# LEDs_Switches.net
KiCad netlist of a schematic drawn in Altium Designer
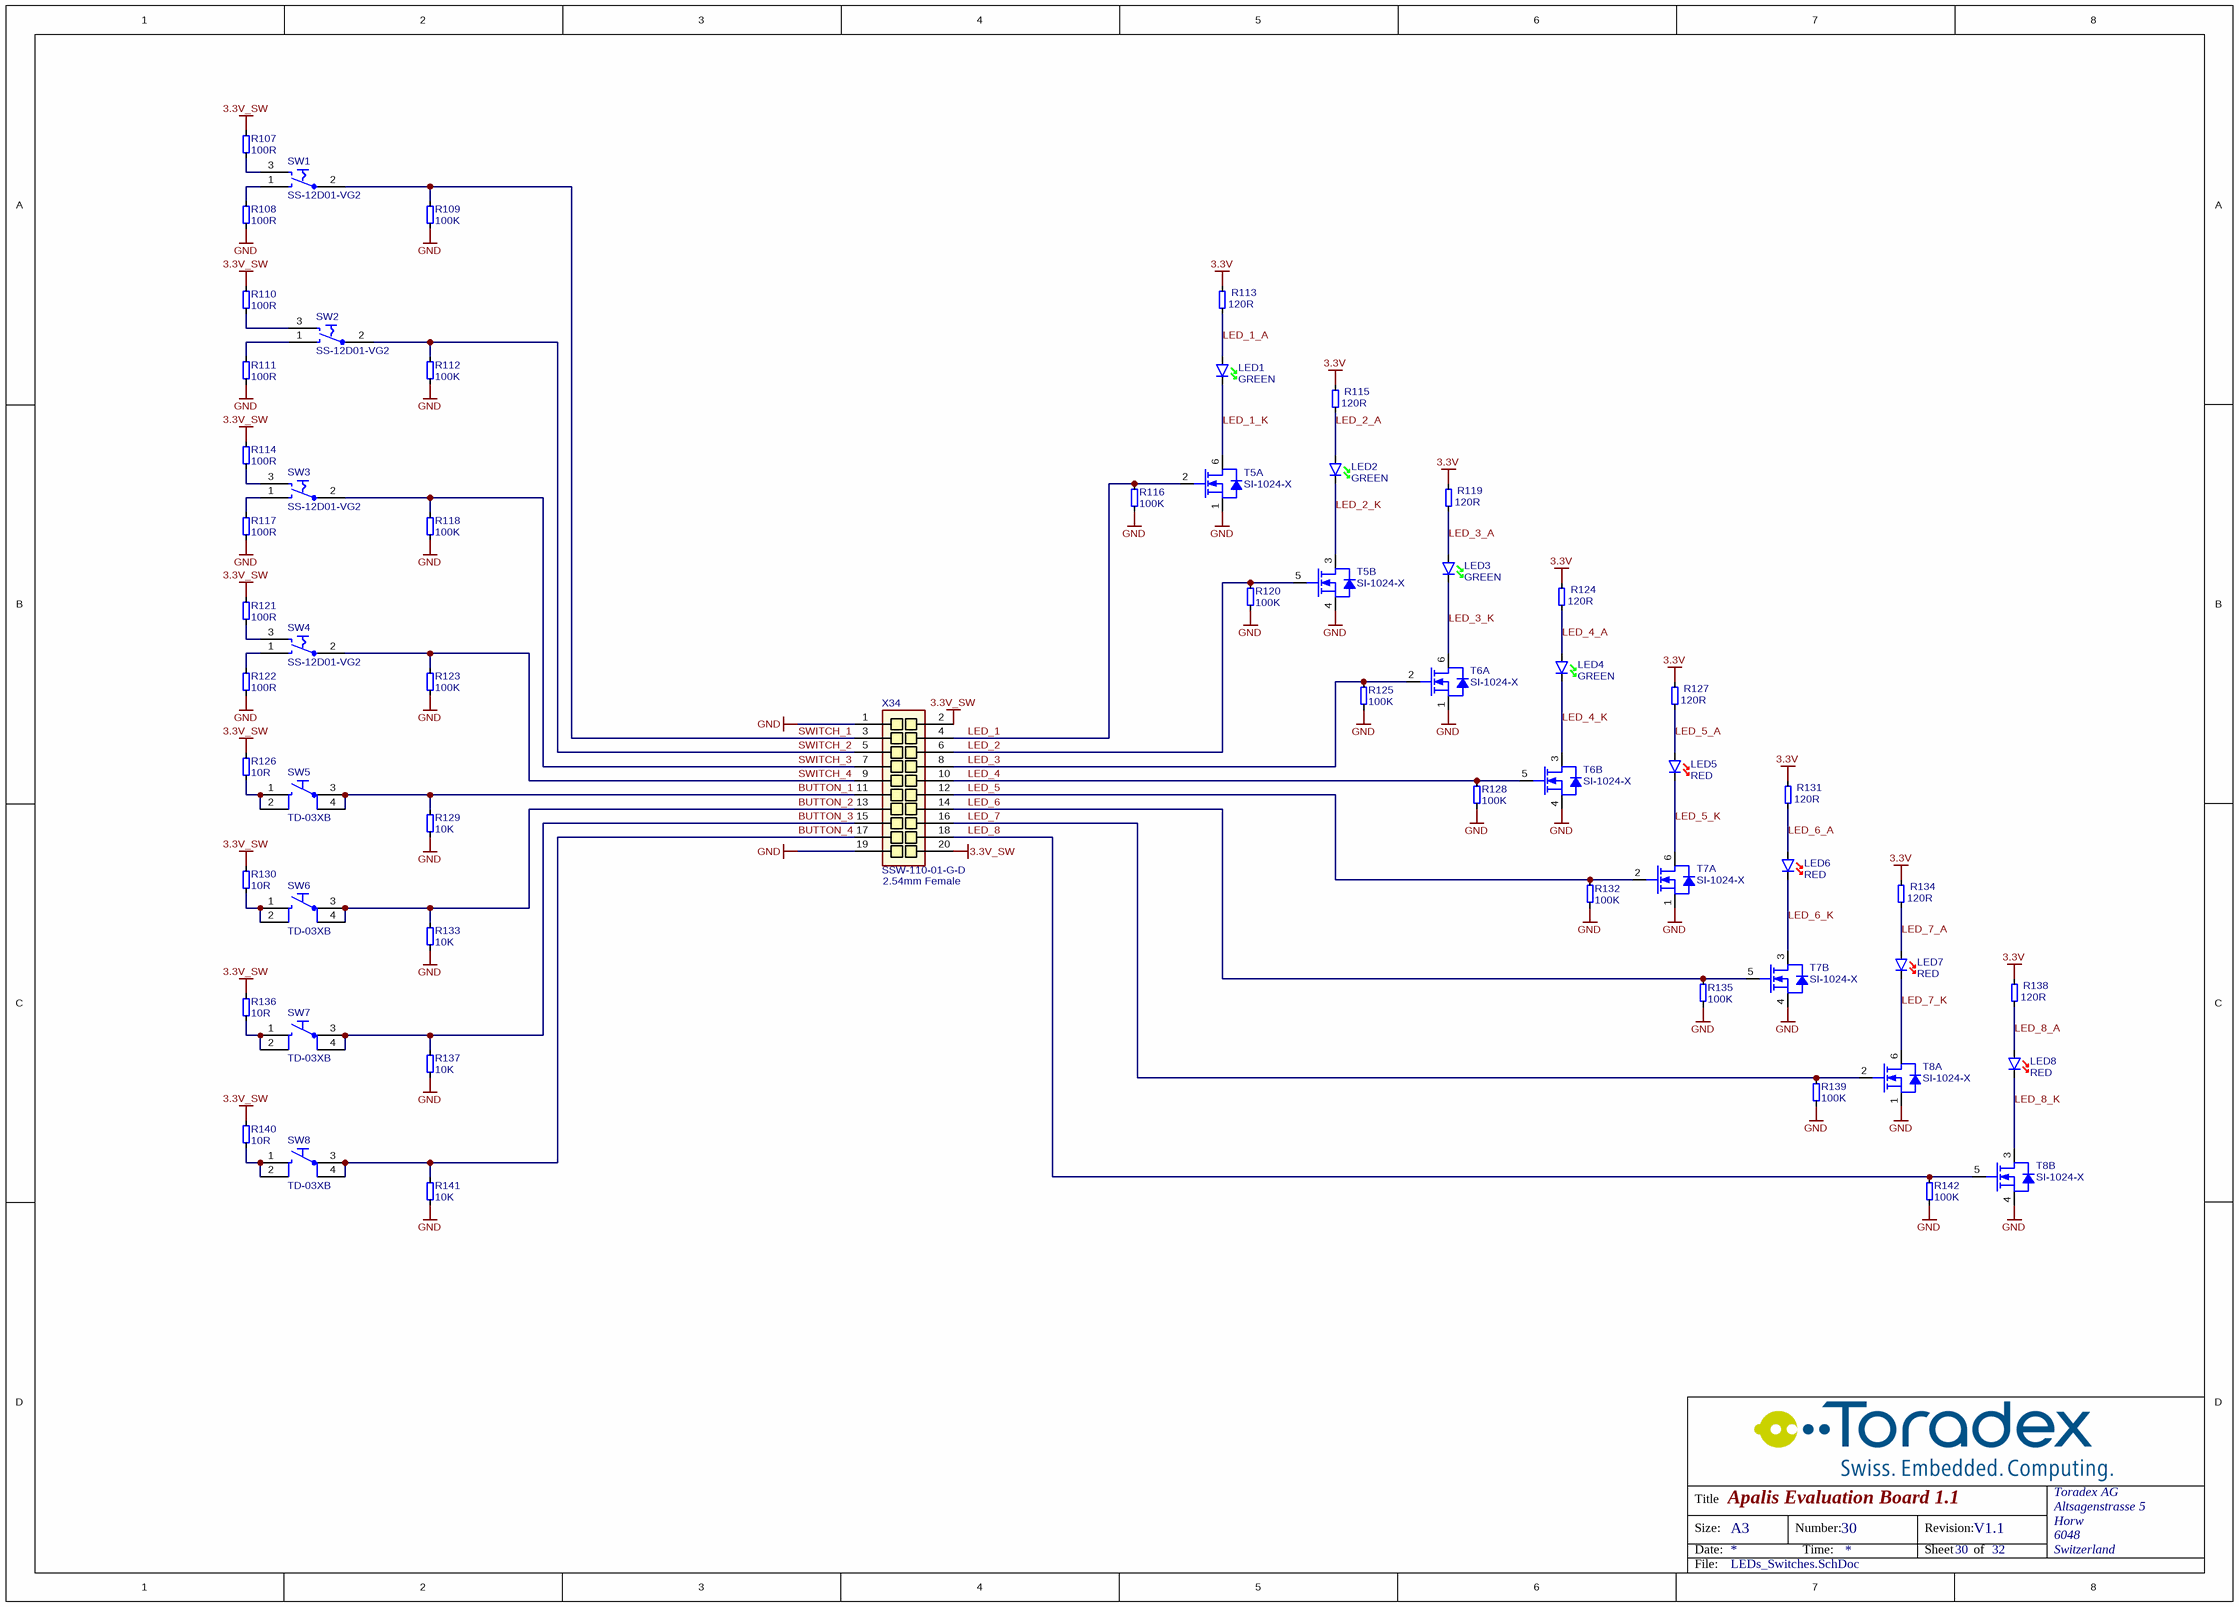
[diagram p0: LEDs_Switches.SchDoc]

(export (version "E")
  (design (tool "Eeschema 10.0.6"))
  (components
    (comp (ref "LED1")
      (value "LG T670-K1L2-1")
      (footprint "T_Osram_T670_GREEN")
      (description "LED green Osram LG T670-K1L2-1")
      (fields (field (name "COLOR") "GREEN"))
      (libsource (lib "Apalis Evaluation Board") (part "LED-Osram-T670-K1L2-1"))
    )
    (comp (ref "LED2")
      (value "LG T670-K1L2-1")
      (footprint "T_Osram_T670_GREEN")
      (description "LED green Osram LG T670-K1L2-1")
      (fields (field (name "COLOR") "GREEN"))
      (libsource (lib "Apalis Evaluation Board") (part "LED-Osram-T670-K1L2-1"))
    )
    (comp (ref "LED3")
      (value "LG T670-K1L2-1")
      (footprint "T_Osram_T670_GREEN")
      (description "LED green Osram LG T670-K1L2-1")
      (fields (field (name "COLOR") "GREEN"))
      (libsource (lib "Apalis Evaluation Board") (part "LED-Osram-T670-K1L2-1"))
    )
    (comp (ref "LED4")
      (value "LG T670-K1L2-1")
      (footprint "T_Osram_T670_GREEN")
      (description "LED green Osram LG T670-K1L2-1")
      (fields (field (name "COLOR") "GREEN"))
      (libsource (lib "Apalis Evaluation Board") (part "LED-Osram-T670-K1L2-1"))
    )
    (comp (ref "LED5")
      (value "LS T670-K1L2-1")
      (footprint "T_Osram_T670_RED")
      (description "LED red, Osram LS T670-K1L2-1")
      (fields (field (name "COLOR") "RED"))
      (libsource (lib "Apalis Evaluation Board") (part "LED-Osram-LS T670-K1L2-1"))
    )
    (comp (ref "LED6")
      (value "LS T670-K1L2-1")
      (footprint "T_Osram_T670_RED")
      (description "LED red, Osram LS T670-K1L2-1")
      (fields (field (name "COLOR") "RED"))
      (libsource (lib "Apalis Evaluation Board") (part "LED-Osram-LS T670-K1L2-1"))
    )
    (comp (ref "LED7")
      (value "LS T670-K1L2-1")
      (footprint "T_Osram_T670_RED")
      (description "LED red, Osram LS T670-K1L2-1")
      (fields (field (name "COLOR") "RED"))
      (libsource (lib "Apalis Evaluation Board") (part "LED-Osram-LS T670-K1L2-1"))
    )
    (comp (ref "LED8")
      (value "LS T670-K1L2-1")
      (footprint "T_Osram_T670_RED")
      (description "LED red, Osram LS T670-K1L2-1")
      (fields (field (name "COLOR") "RED"))
      (libsource (lib "Apalis Evaluation Board") (part "LED-Osram-LS T670-K1L2-1"))
    )
    (comp (ref "R107")
      (value "100R")
      (footprint "T_RESC0603X30N")
      (description "Resistor 100 ohm 63mW 5% 0603")
      (fields (field (name "TOLERANCE") "5%"))
      (libsource (lib "Apalis Evaluation Board") (part "R-100R-63mW-5%-0603"))
    )
    (comp (ref "R108")
      (value "100R")
      (footprint "T_RESC0603X30N")
      (description "Resistor 100 ohm 63mW 5% 0603")
      (fields (field (name "TOLERANCE") "5%"))
      (libsource (lib "Apalis Evaluation Board") (part "R-100R-63mW-5%-0603"))
    )
    (comp (ref "R109")
      (value "100K")
      (footprint "T_RESC0603X30N")
      (description "Resistor 100 Kohm 63mW 5% 0603")
      (fields (field (name "TOLERANCE") "5%"))
      (libsource (lib "Apalis Evaluation Board") (part "R-100KR-63mW-5%-0603"))
    )
    (comp (ref "R110")
      (value "100R")
      (footprint "T_RESC0603X30N")
      (description "Resistor 100 ohm 63mW 5% 0603")
      (fields (field (name "TOLERANCE") "5%"))
      (libsource (lib "Apalis Evaluation Board") (part "R-100R-63mW-5%-0603"))
    )
    (comp (ref "R111")
      (value "100R")
      (footprint "T_RESC0603X30N")
      (description "Resistor 100 ohm 63mW 5% 0603")
      (fields (field (name "TOLERANCE") "5%"))
      (libsource (lib "Apalis Evaluation Board") (part "R-100R-63mW-5%-0603"))
    )
    (comp (ref "R112")
      (value "100K")
      (footprint "T_RESC0603X30N")
      (description "Resistor 100 Kohm 63mW 5% 0603")
      (fields (field (name "TOLERANCE") "5%"))
      (libsource (lib "Apalis Evaluation Board") (part "R-100KR-63mW-5%-0603"))
    )
    (comp (ref "R113")
      (value "120R")
      (footprint "T_RESC0603X30N")
      (description "Resistor 120 ohm 63mW 5% 0603")
      (fields (field (name "TOLERANCE") "5%"))
      (libsource (lib "Apalis Evaluation Board") (part "R-120R-63mW-5%-0603"))
    )
    (comp (ref "R114")
      (value "100R")
      (footprint "T_RESC0603X30N")
      (description "Resistor 100 ohm 63mW 5% 0603")
      (fields (field (name "TOLERANCE") "5%"))
      (libsource (lib "Apalis Evaluation Board") (part "R-100R-63mW-5%-0603"))
    )
    (comp (ref "R115")
      (value "120R")
      (footprint "T_RESC0603X30N")
      (description "Resistor 120 ohm 63mW 5% 0603")
      (fields (field (name "TOLERANCE") "5%"))
      (libsource (lib "Apalis Evaluation Board") (part "R-120R-63mW-5%-0603"))
    )
    (comp (ref "R116")
      (value "100K")
      (footprint "T_RESC0603X30N")
      (description "Resistor 100 Kohm 63mW 5% 0603")
      (fields (field (name "TOLERANCE") "5%"))
      (libsource (lib "Apalis Evaluation Board") (part "R-100KR-63mW-5%-0603"))
    )
    (comp (ref "R117")
      (value "100R")
      (footprint "T_RESC0603X30N")
      (description "Resistor 100 ohm 63mW 5% 0603")
      (fields (field (name "TOLERANCE") "5%"))
      (libsource (lib "Apalis Evaluation Board") (part "R-100R-63mW-5%-0603"))
    )
    (comp (ref "R118")
      (value "100K")
      (footprint "T_RESC0603X30N")
      (description "Resistor 100 Kohm 63mW 5% 0603")
      (fields (field (name "TOLERANCE") "5%"))
      (libsource (lib "Apalis Evaluation Board") (part "R-100KR-63mW-5%-0603"))
    )
    (comp (ref "R119")
      (value "120R")
      (footprint "T_RESC0603X30N")
      (description "Resistor 120 ohm 63mW 5% 0603")
      (fields (field (name "TOLERANCE") "5%"))
      (libsource (lib "Apalis Evaluation Board") (part "R-120R-63mW-5%-0603"))
    )
    (comp (ref "R120")
      (value "100K")
      (footprint "T_RESC0603X30N")
      (description "Resistor 100 Kohm 63mW 5% 0603")
      (fields (field (name "TOLERANCE") "5%"))
      (libsource (lib "Apalis Evaluation Board") (part "R-100KR-63mW-5%-0603"))
    )
    (comp (ref "R121")
      (value "100R")
      (footprint "T_RESC0603X30N")
      (description "Resistor 100 ohm 63mW 5% 0603")
      (fields (field (name "TOLERANCE") "5%"))
      (libsource (lib "Apalis Evaluation Board") (part "R-100R-63mW-5%-0603"))
    )
    (comp (ref "R122")
      (value "100R")
      (footprint "T_RESC0603X30N")
      (description "Resistor 100 ohm 63mW 5% 0603")
      (fields (field (name "TOLERANCE") "5%"))
      (libsource (lib "Apalis Evaluation Board") (part "R-100R-63mW-5%-0603"))
    )
    (comp (ref "R123")
      (value "100K")
      (footprint "T_RESC0603X30N")
      (description "Resistor 100 Kohm 63mW 5% 0603")
      (fields (field (name "TOLERANCE") "5%"))
      (libsource (lib "Apalis Evaluation Board") (part "R-100KR-63mW-5%-0603"))
    )
    (comp (ref "R124")
      (value "120R")
      (footprint "T_RESC0603X30N")
      (description "Resistor 120 ohm 63mW 5% 0603")
      (fields (field (name "TOLERANCE") "5%"))
      (libsource (lib "Apalis Evaluation Board") (part "R-120R-63mW-5%-0603"))
    )
    (comp (ref "R125")
      (value "100K")
      (footprint "T_RESC0603X30N")
      (description "Resistor 100 Kohm 63mW 5% 0603")
      (fields (field (name "TOLERANCE") "5%"))
      (libsource (lib "Apalis Evaluation Board") (part "R-100KR-63mW-5%-0603"))
    )
    (comp (ref "R126")
      (value "10R")
      (footprint "T_RESC0603X30N")
      (description "Resistor 10 ohm 63mW 5% 0603")
      (fields (field (name "TOLERANCE") "5%"))
      (libsource (lib "Apalis Evaluation Board") (part "R-10R-63mW-5%-0603"))
    )
    (comp (ref "R127")
      (value "120R")
      (footprint "T_RESC0603X30N")
      (description "Resistor 120 ohm 63mW 5% 0603")
      (fields (field (name "TOLERANCE") "5%"))
      (libsource (lib "Apalis Evaluation Board") (part "R-120R-63mW-5%-0603"))
    )
    (comp (ref "R128")
      (value "100K")
      (footprint "T_RESC0603X30N")
      (description "Resistor 100 Kohm 63mW 5% 0603")
      (fields (field (name "TOLERANCE") "5%"))
      (libsource (lib "Apalis Evaluation Board") (part "R-100KR-63mW-5%-0603"))
    )
    (comp (ref "R129")
      (value "10K")
      (footprint "T_RESC0603X30N")
      (description "Resistor 10 Kohm 63mW 5% 0603")
      (fields (field (name "TOLERANCE") "5%"))
      (libsource (lib "Apalis Evaluation Board") (part "R-10KR-63mW-5%-0603"))
    )
    (comp (ref "R130")
      (value "10R")
      (footprint "T_RESC0603X30N")
      (description "Resistor 10 ohm 63mW 5% 0603")
      (fields (field (name "TOLERANCE") "5%"))
      (libsource (lib "Apalis Evaluation Board") (part "R-10R-63mW-5%-0603"))
    )
    (comp (ref "R131")
      (value "120R")
      (footprint "T_RESC0603X30N")
      (description "Resistor 120 ohm 63mW 5% 0603")
      (fields (field (name "TOLERANCE") "5%"))
      (libsource (lib "Apalis Evaluation Board") (part "R-120R-63mW-5%-0603"))
    )
    (comp (ref "R132")
      (value "100K")
      (footprint "T_RESC0603X30N")
      (description "Resistor 100 Kohm 63mW 5% 0603")
      (fields (field (name "TOLERANCE") "5%"))
      (libsource (lib "Apalis Evaluation Board") (part "R-100KR-63mW-5%-0603"))
    )
    (comp (ref "R133")
      (value "10K")
      (footprint "T_RESC0603X30N")
      (description "Resistor 10 Kohm 63mW 5% 0603")
      (fields (field (name "TOLERANCE") "5%"))
      (libsource (lib "Apalis Evaluation Board") (part "R-10KR-63mW-5%-0603"))
    )
    (comp (ref "R134")
      (value "120R")
      (footprint "T_RESC0603X30N")
      (description "Resistor 120 ohm 63mW 5% 0603")
      (fields (field (name "TOLERANCE") "5%"))
      (libsource (lib "Apalis Evaluation Board") (part "R-120R-63mW-5%-0603"))
    )
    (comp (ref "R135")
      (value "100K")
      (footprint "T_RESC0603X30N")
      (description "Resistor 100 Kohm 63mW 5% 0603")
      (fields (field (name "TOLERANCE") "5%"))
      (libsource (lib "Apalis Evaluation Board") (part "R-100KR-63mW-5%-0603"))
    )
    (comp (ref "R136")
      (value "10R")
      (footprint "T_RESC0603X30N")
      (description "Resistor 10 ohm 63mW 5% 0603")
      (fields (field (name "TOLERANCE") "5%"))
      (libsource (lib "Apalis Evaluation Board") (part "R-10R-63mW-5%-0603"))
    )
    (comp (ref "R137")
      (value "10K")
      (footprint "T_RESC0603X30N")
      (description "Resistor 10 Kohm 63mW 5% 0603")
      (fields (field (name "TOLERANCE") "5%"))
      (libsource (lib "Apalis Evaluation Board") (part "R-10KR-63mW-5%-0603"))
    )
    (comp (ref "R138")
      (value "120R")
      (footprint "T_RESC0603X30N")
      (description "Resistor 120 ohm 63mW 5% 0603")
      (fields (field (name "TOLERANCE") "5%"))
      (libsource (lib "Apalis Evaluation Board") (part "R-120R-63mW-5%-0603"))
    )
    (comp (ref "R139")
      (value "100K")
      (footprint "T_RESC0603X30N")
      (description "Resistor 100 Kohm 63mW 5% 0603")
      (fields (field (name "TOLERANCE") "5%"))
      (libsource (lib "Apalis Evaluation Board") (part "R-100KR-63mW-5%-0603"))
    )
    (comp (ref "R140")
      (value "10R")
      (footprint "T_RESC0603X30N")
      (description "Resistor 10 ohm 63mW 5% 0603")
      (fields (field (name "TOLERANCE") "5%"))
      (libsource (lib "Apalis Evaluation Board") (part "R-10R-63mW-5%-0603"))
    )
    (comp (ref "R141")
      (value "10K")
      (footprint "T_RESC0603X30N")
      (description "Resistor 10 Kohm 63mW 5% 0603")
      (fields (field (name "TOLERANCE") "5%"))
      (libsource (lib "Apalis Evaluation Board") (part "R-10KR-63mW-5%-0603"))
    )
    (comp (ref "R142")
      (value "100K")
      (footprint "T_RESC0603X30N")
      (description "Resistor 100 Kohm 63mW 5% 0603")
      (fields (field (name "TOLERANCE") "5%"))
      (libsource (lib "Apalis Evaluation Board") (part "R-100KR-63mW-5%-0603"))
    )
    (comp (ref "SW1")
      (value "SS-12D01-VG2")
      (footprint "T_See-Plus_SS-12D01-VG2")
      (description "Switch")
      (libsource (lib "") (part "SW-See-Plus-SS-12D01-VG2_1"))
    )
    (comp (ref "SW2")
      (value "SS-12D01-VG2")
      (footprint "T_See-Plus_SS-12D01-VG2")
      (description "Switch")
      (libsource (lib "Apalis Evaluation Board") (part "SW-See-Plus-SS-12D01-VG2"))
    )
    (comp (ref "SW3")
      (value "SS-12D01-VG2")
      (footprint "T_See-Plus_SS-12D01-VG2")
      (description "Switch")
      (libsource (lib "Apalis Evaluation Board") (part "SW-See-Plus-SS-12D01-VG2"))
    )
    (comp (ref "SW4")
      (value "SS-12D01-VG2")
      (footprint "T_See-Plus_SS-12D01-VG2")
      (description "Switch")
      (libsource (lib "Apalis Evaluation Board") (part "SW-See-Plus-SS-12D01-VG2"))
    )
    (comp (ref "SW5")
      (value "TD-03XB")
      (footprint "T_WMF_TD-03XB")
      (description "Push Button")
      (libsource (lib "Apalis Evaluation Board") (part "SW-WMF-TD-03XB"))
    )
    (comp (ref "SW6")
      (value "TD-03XB")
      (footprint "T_WMF_TD-03XB")
      (description "Push Button")
      (libsource (lib "Apalis Evaluation Board") (part "SW-WMF-TD-03XB"))
    )
    (comp (ref "SW7")
      (value "TD-03XB")
      (footprint "T_WMF_TD-03XB")
      (description "Push Button")
      (libsource (lib "Apalis Evaluation Board") (part "SW-WMF-TD-03XB"))
    )
    (comp (ref "SW8")
      (value "TD-03XB")
      (footprint "T_WMF_TD-03XB")
      (description "Push Button")
      (libsource (lib "Apalis Evaluation Board") (part "SW-WMF-TD-03XB"))
    )
    (comp (ref "T5")
      (value "T-Vishay-SI-1024X-N")
      (footprint "SOTFL50P160X60-6N")
      (description "Dual N-Channel 20V (D-S)  MOSFET")
      (fields (field (name "MANUFACTURER PART NO.") "SI-1024-X"))
      (libsource (lib "Apalis Evaluation Board") (part "T-Vishay-SI-1024X-N"))
    )
    (comp (ref "T6")
      (value "T-Vishay-SI-1024X-N")
      (footprint "SOTFL50P160X60-6N")
      (description "Dual N-Channel 20V (D-S)  MOSFET")
      (fields (field (name "MANUFACTURER PART NO.") "SI-1024-X"))
      (libsource (lib "Apalis Evaluation Board") (part "T-Vishay-SI-1024X-N"))
    )
    (comp (ref "T7")
      (value "T-Vishay-SI-1024X-N")
      (footprint "SOTFL50P160X60-6N")
      (description "Dual N-Channel 20V (D-S)  MOSFET")
      (fields (field (name "MANUFACTURER PART NO.") "SI-1024-X"))
      (libsource (lib "Apalis Evaluation Board") (part "T-Vishay-SI-1024X-N"))
    )
    (comp (ref "T8")
      (value "T-Vishay-SI-1024X-N")
      (footprint "SOTFL50P160X60-6N")
      (description "Dual N-Channel 20V (D-S)  MOSFET")
      (fields (field (name "MANUFACTURER PART NO.") "SI-1024-X"))
      (libsource (lib "Apalis Evaluation Board") (part "T-Vishay-SI-1024X-N"))
    )
    (comp (ref "X34")
      (value "SSW-110-01-G-D")
      (footprint "T_Samtec_SSW-110-01-G-D")
      (description "Receptacle Female Socket 2x10 Pins, 2.54 mm pitch")
      (fields (field (name "MANUFACTURER PART NO.") "SSW-110-01-G-D"))
      (libsource (lib "Apalis Evaluation Board") (part "CON-Samtec-SSW-110-01-G-D"))
    )
  )
  (nets
    (net (code "1") (name "/BUTTON_1") (class "Default")
      (node (ref "R129") (pin "2") (pinfunction "2_2") (pintype "passive"))
      (node (ref "SW5") (pin "3") (pinfunction "3_3") (pintype "passive"))
      (node (ref "SW5") (pin "4") (pinfunction "4_4") (pintype "passive"))
      (node (ref "X34") (pin "11") (pinfunction "11_11") (pintype "passive"))
    )
    (net (code "2") (name "/BUTTON_2") (class "Default")
      (node (ref "R133") (pin "2") (pinfunction "2_2") (pintype "passive"))
      (node (ref "SW6") (pin "3") (pinfunction "3_3") (pintype "passive"))
      (node (ref "SW6") (pin "4") (pinfunction "4_4") (pintype "passive"))
      (node (ref "X34") (pin "13") (pinfunction "13_13") (pintype "passive"))
    )
    (net (code "3") (name "/BUTTON_3") (class "Default")
      (node (ref "R137") (pin "2") (pinfunction "2_2") (pintype "passive"))
      (node (ref "SW7") (pin "3") (pinfunction "3_3") (pintype "passive"))
      (node (ref "SW7") (pin "4") (pinfunction "4_4") (pintype "passive"))
      (node (ref "X34") (pin "15") (pinfunction "15_15") (pintype "passive"))
    )
    (net (code "4") (name "/BUTTON_4") (class "Default")
      (node (ref "R141") (pin "2") (pinfunction "2_2") (pintype "passive"))
      (node (ref "SW8") (pin "3") (pinfunction "3_3") (pintype "passive"))
      (node (ref "SW8") (pin "4") (pinfunction "4_4") (pintype "passive"))
      (node (ref "X34") (pin "17") (pinfunction "17_17") (pintype "passive"))
    )
    (net (code "5") (name "/LED_1") (class "Default")
      (node (ref "R116") (pin "2") (pinfunction "2_2") (pintype "passive"))
      (node (ref "T5") (pin "2") (pinfunction "G_2") (pintype "passive"))
      (node (ref "X34") (pin "4") (pinfunction "4_4") (pintype "passive"))
    )
    (net (code "6") (name "/LED_1_A") (class "Default")
      (node (ref "LED1") (pin "A") (pinfunction "A_A") (pintype "passive"))
      (node (ref "R113") (pin "1") (pinfunction "1_1") (pintype "passive"))
    )
    (net (code "7") (name "/LED_1_K") (class "Default")
      (node (ref "LED1") (pin "K") (pinfunction "K_K") (pintype "passive"))
      (node (ref "T5") (pin "6") (pinfunction "D_6") (pintype "passive"))
    )
    (net (code "8") (name "/LED_2") (class "Default")
      (node (ref "R120") (pin "2") (pinfunction "2_2") (pintype "passive"))
      (node (ref "T5") (pin "5") (pinfunction "G_5") (pintype "passive"))
      (node (ref "X34") (pin "6") (pinfunction "6_6") (pintype "passive"))
    )
    (net (code "9") (name "/LED_2_A") (class "Default")
      (node (ref "LED2") (pin "A") (pinfunction "A_A") (pintype "passive"))
      (node (ref "R115") (pin "1") (pinfunction "1_1") (pintype "passive"))
    )
    (net (code "10") (name "/LED_2_K") (class "Default")
      (node (ref "LED2") (pin "K") (pinfunction "K_K") (pintype "passive"))
      (node (ref "T5") (pin "3") (pinfunction "D_3") (pintype "passive"))
    )
    (net (code "11") (name "/LED_3") (class "Default")
      (node (ref "R125") (pin "2") (pinfunction "2_2") (pintype "passive"))
      (node (ref "T6") (pin "2") (pinfunction "G_2") (pintype "passive"))
      (node (ref "X34") (pin "8") (pinfunction "8_8") (pintype "passive"))
    )
    (net (code "12") (name "/LED_3_A") (class "Default")
      (node (ref "LED3") (pin "A") (pinfunction "A_A") (pintype "passive"))
      (node (ref "R119") (pin "1") (pinfunction "1_1") (pintype "passive"))
    )
    (net (code "13") (name "/LED_3_K") (class "Default")
      (node (ref "LED3") (pin "K") (pinfunction "K_K") (pintype "passive"))
      (node (ref "T6") (pin "6") (pinfunction "D_6") (pintype "passive"))
    )
    (net (code "14") (name "/LED_4") (class "Default")
      (node (ref "R128") (pin "2") (pinfunction "2_2") (pintype "passive"))
      (node (ref "T6") (pin "5") (pinfunction "G_5") (pintype "passive"))
      (node (ref "X34") (pin "10") (pinfunction "10_10") (pintype "passive"))
    )
    (net (code "15") (name "/LED_4_A") (class "Default")
      (node (ref "LED4") (pin "A") (pinfunction "A_A") (pintype "passive"))
      (node (ref "R124") (pin "1") (pinfunction "1_1") (pintype "passive"))
    )
    (net (code "16") (name "/LED_4_K") (class "Default")
      (node (ref "LED4") (pin "K") (pinfunction "K_K") (pintype "passive"))
      (node (ref "T6") (pin "3") (pinfunction "D_3") (pintype "passive"))
    )
    (net (code "17") (name "/LED_5") (class "Default")
      (node (ref "R132") (pin "2") (pinfunction "2_2") (pintype "passive"))
      (node (ref "T7") (pin "2") (pinfunction "G_2") (pintype "passive"))
      (node (ref "X34") (pin "12") (pinfunction "12_12") (pintype "passive"))
    )
    (net (code "18") (name "/LED_5_A") (class "Default")
      (node (ref "LED5") (pin "A") (pinfunction "A_A") (pintype "passive"))
      (node (ref "R127") (pin "1") (pinfunction "1_1") (pintype "passive"))
    )
    (net (code "19") (name "/LED_5_K") (class "Default")
      (node (ref "LED5") (pin "K") (pinfunction "K_K") (pintype "passive"))
      (node (ref "T7") (pin "6") (pinfunction "D_6") (pintype "passive"))
    )
    (net (code "20") (name "/LED_6") (class "Default")
      (node (ref "R135") (pin "2") (pinfunction "2_2") (pintype "passive"))
      (node (ref "T7") (pin "5") (pinfunction "G_5") (pintype "passive"))
      (node (ref "X34") (pin "14") (pinfunction "14_14") (pintype "passive"))
    )
    (net (code "21") (name "/LED_6_A") (class "Default")
      (node (ref "LED6") (pin "A") (pinfunction "A_A") (pintype "passive"))
      (node (ref "R131") (pin "1") (pinfunction "1_1") (pintype "passive"))
    )
    (net (code "22") (name "/LED_6_K") (class "Default")
      (node (ref "LED6") (pin "K") (pinfunction "K_K") (pintype "passive"))
      (node (ref "T7") (pin "3") (pinfunction "D_3") (pintype "passive"))
    )
    (net (code "23") (name "/LED_7") (class "Default")
      (node (ref "R139") (pin "2") (pinfunction "2_2") (pintype "passive"))
      (node (ref "T8") (pin "2") (pinfunction "G_2") (pintype "passive"))
      (node (ref "X34") (pin "16") (pinfunction "16_16") (pintype "passive"))
    )
    (net (code "24") (name "/LED_7_A") (class "Default")
      (node (ref "LED7") (pin "A") (pinfunction "A_A") (pintype "passive"))
      (node (ref "R134") (pin "1") (pinfunction "1_1") (pintype "passive"))
    )
    (net (code "25") (name "/LED_7_K") (class "Default")
      (node (ref "LED7") (pin "K") (pinfunction "K_K") (pintype "passive"))
      (node (ref "T8") (pin "6") (pinfunction "D_6") (pintype "passive"))
    )
    (net (code "26") (name "/LED_8") (class "Default")
      (node (ref "R142") (pin "2") (pinfunction "2_2") (pintype "passive"))
      (node (ref "T8") (pin "5") (pinfunction "G_5") (pintype "passive"))
      (node (ref "X34") (pin "18") (pinfunction "18_18") (pintype "passive"))
    )
    (net (code "27") (name "/LED_8_A") (class "Default")
      (node (ref "LED8") (pin "A") (pinfunction "A_A") (pintype "passive"))
      (node (ref "R138") (pin "1") (pinfunction "1_1") (pintype "passive"))
    )
    (net (code "28") (name "/LED_8_K") (class "Default")
      (node (ref "LED8") (pin "K") (pinfunction "K_K") (pintype "passive"))
      (node (ref "T8") (pin "3") (pinfunction "D_3") (pintype "passive"))
    )
    (net (code "29") (name "/SWITCH_1") (class "Default")
      (node (ref "R109") (pin "2") (pinfunction "2_2") (pintype "passive"))
      (node (ref "SW1") (pin "2") (pinfunction "2_2") (pintype "passive"))
      (node (ref "X34") (pin "3") (pinfunction "3_3") (pintype "passive"))
    )
    (net (code "30") (name "/SWITCH_2") (class "Default")
      (node (ref "R112") (pin "2") (pinfunction "2_2") (pintype "passive"))
      (node (ref "SW2") (pin "2") (pinfunction "2_2") (pintype "passive"))
      (node (ref "X34") (pin "5") (pinfunction "5_5") (pintype "passive"))
    )
    (net (code "31") (name "/SWITCH_3") (class "Default")
      (node (ref "R118") (pin "2") (pinfunction "2_2") (pintype "passive"))
      (node (ref "SW3") (pin "2") (pinfunction "2_2") (pintype "passive"))
      (node (ref "X34") (pin "7") (pinfunction "7_7") (pintype "passive"))
    )
    (net (code "32") (name "/SWITCH_4") (class "Default")
      (node (ref "R123") (pin "2") (pinfunction "2_2") (pintype "passive"))
      (node (ref "SW4") (pin "2") (pinfunction "2_2") (pintype "passive"))
      (node (ref "X34") (pin "9") (pinfunction "9_9") (pintype "passive"))
    )
    (net (code "33") (name "3.3V") (class "Default")
      (node (ref "R113") (pin "2") (pinfunction "2_2") (pintype "passive"))
      (node (ref "R115") (pin "2") (pinfunction "2_2") (pintype "passive"))
      (node (ref "R119") (pin "2") (pinfunction "2_2") (pintype "passive"))
      (node (ref "R124") (pin "2") (pinfunction "2_2") (pintype "passive"))
      (node (ref "R127") (pin "2") (pinfunction "2_2") (pintype "passive"))
      (node (ref "R131") (pin "2") (pinfunction "2_2") (pintype "passive"))
      (node (ref "R134") (pin "2") (pinfunction "2_2") (pintype "passive"))
      (node (ref "R138") (pin "2") (pinfunction "2_2") (pintype "passive"))
    )
    (net (code "34") (name "3.3V_SW") (class "Default")
      (node (ref "R107") (pin "2") (pinfunction "2_2") (pintype "passive"))
      (node (ref "R110") (pin "2") (pinfunction "2_2") (pintype "passive"))
      (node (ref "R114") (pin "2") (pinfunction "2_2") (pintype "passive"))
      (node (ref "R121") (pin "2") (pinfunction "2_2") (pintype "passive"))
      (node (ref "R126") (pin "2") (pinfunction "2_2") (pintype "passive"))
      (node (ref "R130") (pin "2") (pinfunction "2_2") (pintype "passive"))
      (node (ref "R136") (pin "2") (pinfunction "2_2") (pintype "passive"))
      (node (ref "R140") (pin "2") (pinfunction "2_2") (pintype "passive"))
      (node (ref "X34") (pin "2") (pinfunction "2_2") (pintype "passive"))
      (node (ref "X34") (pin "20") (pinfunction "20_20") (pintype "passive"))
    )
    (net (code "35") (name "GND") (class "Default")
      (node (ref "R108") (pin "1") (pinfunction "1_1") (pintype "passive"))
      (node (ref "R109") (pin "1") (pinfunction "1_1") (pintype "passive"))
      (node (ref "R111") (pin "1") (pinfunction "1_1") (pintype "passive"))
      (node (ref "R112") (pin "1") (pinfunction "1_1") (pintype "passive"))
      (node (ref "R116") (pin "1") (pinfunction "1_1") (pintype "passive"))
      (node (ref "R117") (pin "1") (pinfunction "1_1") (pintype "passive"))
      (node (ref "R118") (pin "1") (pinfunction "1_1") (pintype "passive"))
      (node (ref "R120") (pin "1") (pinfunction "1_1") (pintype "passive"))
      (node (ref "R122") (pin "1") (pinfunction "1_1") (pintype "passive"))
      (node (ref "R123") (pin "1") (pinfunction "1_1") (pintype "passive"))
      (node (ref "R125") (pin "1") (pinfunction "1_1") (pintype "passive"))
      (node (ref "R128") (pin "1") (pinfunction "1_1") (pintype "passive"))
      (node (ref "R129") (pin "1") (pinfunction "1_1") (pintype "passive"))
      (node (ref "R132") (pin "1") (pinfunction "1_1") (pintype "passive"))
      (node (ref "R133") (pin "1") (pinfunction "1_1") (pintype "passive"))
      (node (ref "R135") (pin "1") (pinfunction "1_1") (pintype "passive"))
      (node (ref "R137") (pin "1") (pinfunction "1_1") (pintype "passive"))
      (node (ref "R139") (pin "1") (pinfunction "1_1") (pintype "passive"))
      (node (ref "R141") (pin "1") (pinfunction "1_1") (pintype "passive"))
      (node (ref "R142") (pin "1") (pinfunction "1_1") (pintype "passive"))
      (node (ref "T5") (pin "1") (pinfunction "S_1") (pintype "passive"))
      (node (ref "T5") (pin "4") (pinfunction "S_4") (pintype "passive"))
      (node (ref "T6") (pin "1") (pinfunction "S_1") (pintype "passive"))
      (node (ref "T6") (pin "4") (pinfunction "S_4") (pintype "passive"))
      (node (ref "T7") (pin "1") (pinfunction "S_1") (pintype "passive"))
      (node (ref "T7") (pin "4") (pinfunction "S_4") (pintype "passive"))
      (node (ref "T8") (pin "1") (pinfunction "S_1") (pintype "passive"))
      (node (ref "T8") (pin "4") (pinfunction "S_4") (pintype "passive"))
      (node (ref "X34") (pin "1") (pinfunction "1_1") (pintype "passive"))
      (node (ref "X34") (pin "19") (pinfunction "19_19") (pintype "passive"))
    )
    (net (code "36") (name "Net-(R107-Pad1)") (class "Default")
      (node (ref "R107") (pin "1") (pinfunction "1_1") (pintype "passive"))
      (node (ref "SW1") (pin "3") (pinfunction "3_3") (pintype "passive"))
    )
    (net (code "37") (name "Net-(R108-Pad2)") (class "Default")
      (node (ref "R108") (pin "2") (pinfunction "2_2") (pintype "passive"))
      (node (ref "SW1") (pin "1") (pinfunction "1_1") (pintype "passive"))
    )
    (net (code "38") (name "Net-(R110-Pad1)") (class "Default")
      (node (ref "R110") (pin "1") (pinfunction "1_1") (pintype "passive"))
      (node (ref "SW2") (pin "3") (pinfunction "3_3") (pintype "passive"))
    )
    (net (code "39") (name "Net-(R111-Pad2)") (class "Default")
      (node (ref "R111") (pin "2") (pinfunction "2_2") (pintype "passive"))
      (node (ref "SW2") (pin "1") (pinfunction "1_1") (pintype "passive"))
    )
    (net (code "40") (name "Net-(R114-Pad1)") (class "Default")
      (node (ref "R114") (pin "1") (pinfunction "1_1") (pintype "passive"))
      (node (ref "SW3") (pin "3") (pinfunction "3_3") (pintype "passive"))
    )
    (net (code "41") (name "Net-(R117-Pad2)") (class "Default")
      (node (ref "R117") (pin "2") (pinfunction "2_2") (pintype "passive"))
      (node (ref "SW3") (pin "1") (pinfunction "1_1") (pintype "passive"))
    )
    (net (code "42") (name "Net-(R121-Pad1)") (class "Default")
      (node (ref "R121") (pin "1") (pinfunction "1_1") (pintype "passive"))
      (node (ref "SW4") (pin "3") (pinfunction "3_3") (pintype "passive"))
    )
    (net (code "43") (name "Net-(R122-Pad2)") (class "Default")
      (node (ref "R122") (pin "2") (pinfunction "2_2") (pintype "passive"))
      (node (ref "SW4") (pin "1") (pinfunction "1_1") (pintype "passive"))
    )
    (net (code "44") (name "Net-(R126-Pad1)") (class "Default")
      (node (ref "R126") (pin "1") (pinfunction "1_1") (pintype "passive"))
      (node (ref "SW5") (pin "1") (pinfunction "1_1") (pintype "passive"))
      (node (ref "SW5") (pin "2") (pinfunction "2_2") (pintype "passive"))
    )
    (net (code "45") (name "Net-(R130-Pad1)") (class "Default")
      (node (ref "R130") (pin "1") (pinfunction "1_1") (pintype "passive"))
      (node (ref "SW6") (pin "1") (pinfunction "1_1") (pintype "passive"))
      (node (ref "SW6") (pin "2") (pinfunction "2_2") (pintype "passive"))
    )
    (net (code "46") (name "Net-(R136-Pad1)") (class "Default")
      (node (ref "R136") (pin "1") (pinfunction "1_1") (pintype "passive"))
      (node (ref "SW7") (pin "1") (pinfunction "1_1") (pintype "passive"))
      (node (ref "SW7") (pin "2") (pinfunction "2_2") (pintype "passive"))
    )
    (net (code "47") (name "Net-(R140-Pad1)") (class "Default")
      (node (ref "R140") (pin "1") (pinfunction "1_1") (pintype "passive"))
      (node (ref "SW8") (pin "1") (pinfunction "1_1") (pintype "passive"))
      (node (ref "SW8") (pin "2") (pinfunction "2_2") (pintype "passive"))
    )
  )
)
